# water-pump.net
KiCad netlist of a schematic drawn in EAGLE
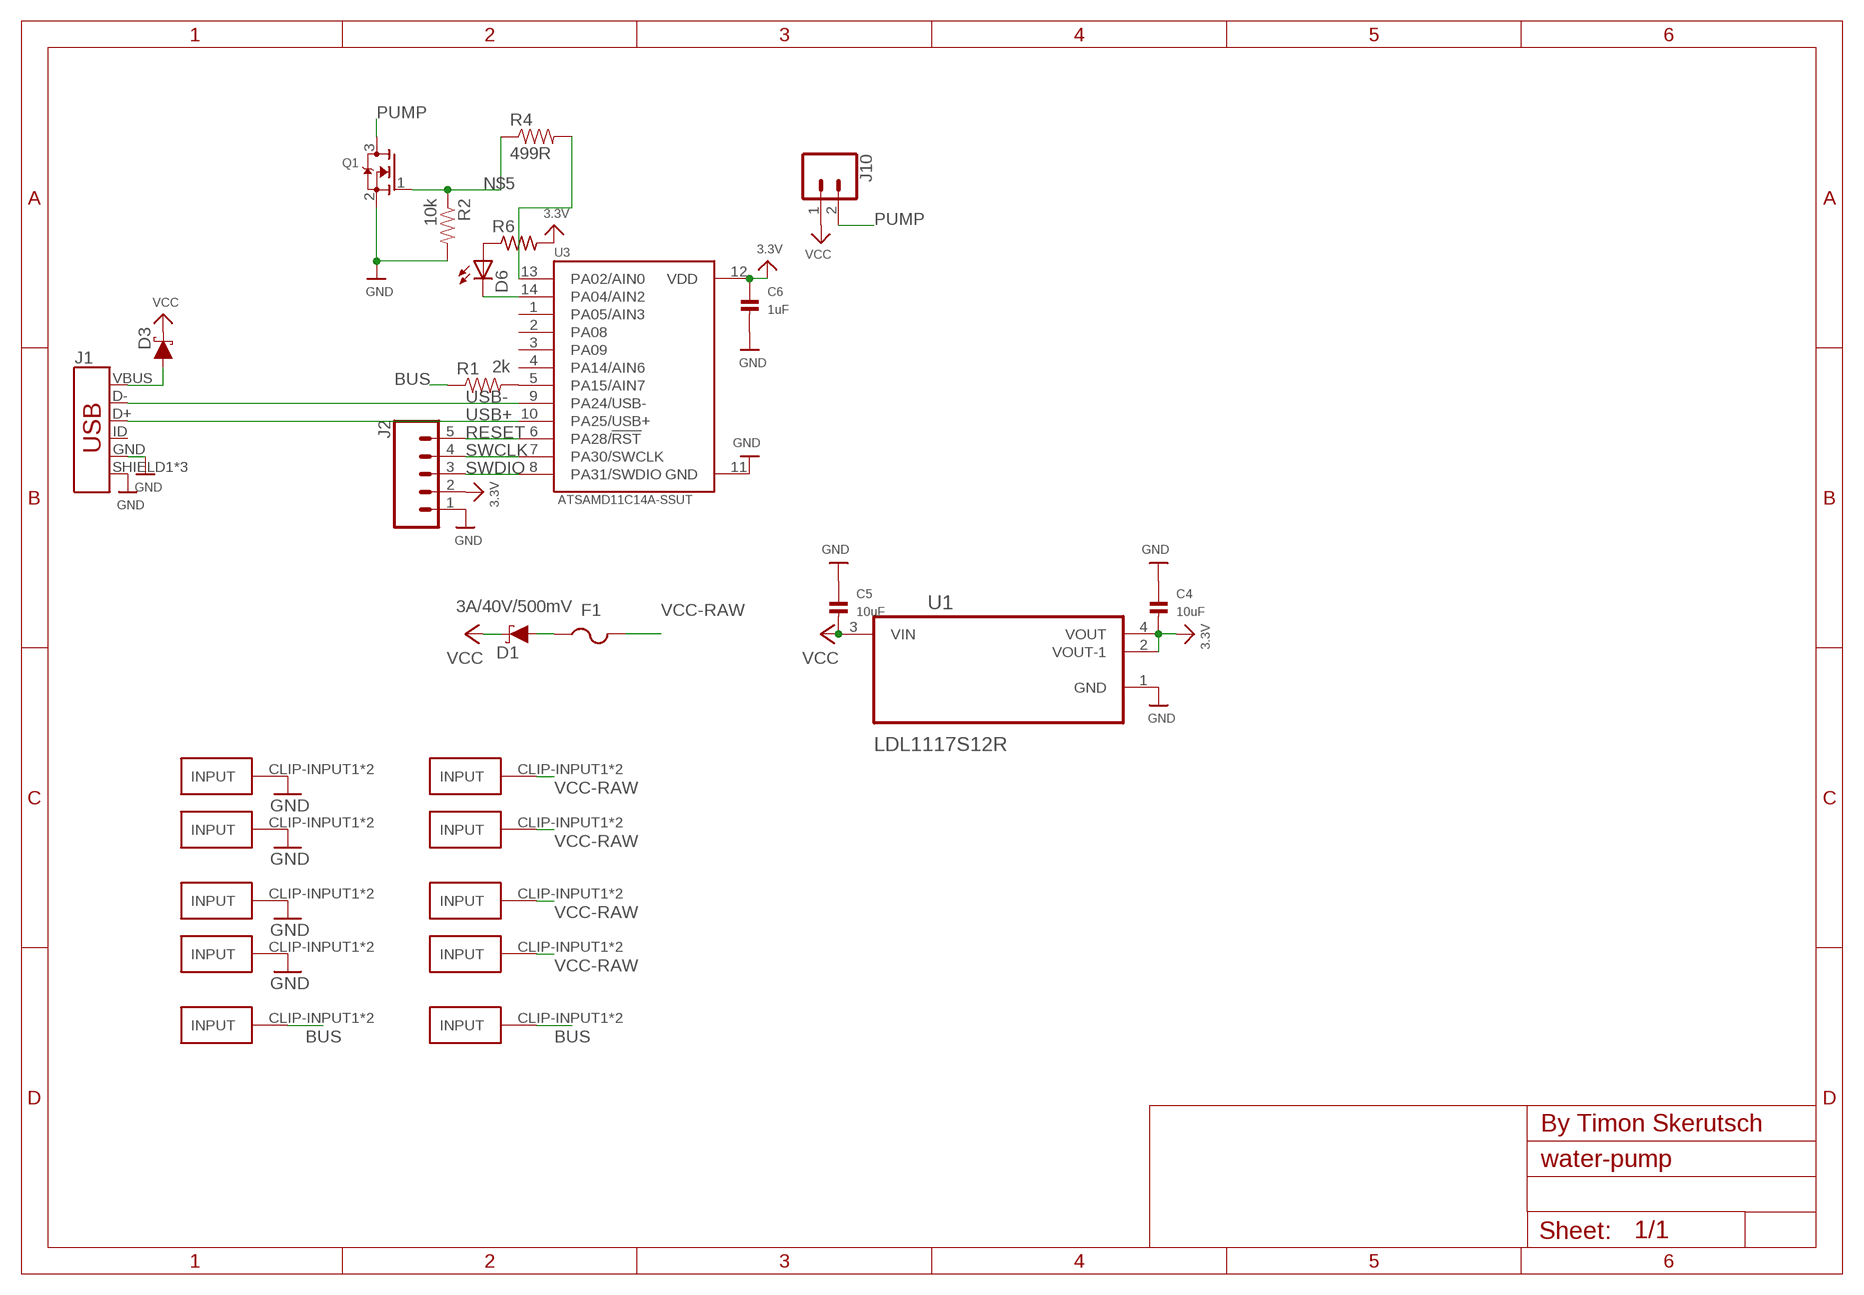
[diagram p0: schematic, sheet 1]

(export (version "E")
  (design (tool "Eeschema 10.0.6"))
  (components
    (comp (ref "C4")
      (value "10uF")
      (footprint "eagle-import:0805")
      (libsource (lib "eagle-import") (part "CAP_CERAMIC0805"))
    )
    (comp (ref "C5")
      (value "10uF")
      (footprint "eagle-import:0805")
      (libsource (lib "eagle-import") (part "CAP_CERAMIC0805"))
    )
    (comp (ref "C6")
      (value "1uF")
      (footprint "eagle-import:0603")
      (libsource (lib "eagle-import") (part "CAP_CERAMIC0603"))
    )
    (comp (ref "D1")
      (value "3A/40V/500mV")
      (footprint "eagle-import:SMA-DIODE")
      (libsource (lib "eagle-import") (part "DIODE-SCHOTTKY-B340A"))
    )
    (comp (ref "D3")
      (value "3A/40V/500mV")
      (footprint "eagle-import:SMA-DIODE")
      (libsource (lib "eagle-import") (part "DIODE-SCHOTTKY-B340A"))
    )
    (comp (ref "D6")
      (value "LEDCHIPLED_0805")
      (footprint "eagle-import:CHIPLED_0805")
      (libsource (lib "eagle-import") (part "LEDCHIPLED_0805"))
    )
    (comp (ref "F1")
      (value "PTCFUSE-1812")
      (footprint "eagle-import:1812")
      (libsource (lib "eagle-import") (part "PTCFUSE-1812"))
    )
    (comp (ref "GND-CLIP")
      (value "FUSE-HOLDER-5X20MM")
      (footprint "eagle-import:FUSE-HOLDER-5X20MM")
      (libsource (lib "eagle-import") (part "FUSE-HOLDER-5X20MM"))
    )
    (comp (ref "GND-CLIP1")
      (value "FUSE-HOLDER-5X20MM")
      (footprint "eagle-import:FUSE-HOLDER-5X20MM")
      (libsource (lib "eagle-import") (part "FUSE-HOLDER-5X20MM"))
    )
    (comp (ref "GND-CLIP2")
      (value "FUSE-HOLDER-5X20MM")
      (footprint "eagle-import:FUSE-HOLDER-5X20MM")
      (libsource (lib "eagle-import") (part "FUSE-HOLDER-5X20MM"))
    )
    (comp (ref "GND-CLIP3")
      (value "FUSE-HOLDER-5X20MM")
      (footprint "eagle-import:FUSE-HOLDER-5X20MM")
      (libsource (lib "eagle-import") (part "FUSE-HOLDER-5X20MM"))
    )
    (comp (ref "J1")
      (value "USB_MICRO-B_FEMALE-SMT")
      (footprint "eagle-import:USB-B-MICRO-SMD")
      (libsource (lib "eagle-import") (part "USB_MICRO-B_FEMALE-SMT"))
    )
    (comp (ref "J2")
      (value "CONN_05")
      (footprint "eagle-import:1X05")
      (libsource (lib "eagle-import") (part "CONN_05"))
    )
    (comp (ref "J10")
      (value "CONN_02PTH3")
      (footprint "eagle-import:1X02_LONGPADS")
      (libsource (lib "eagle-import") (part "CONN_02PTH3"))
    )
    (comp (ref "PWM-CLIP")
      (value "FUSE-HOLDER-5X20MM")
      (footprint "eagle-import:FUSE-HOLDER-5X20MM")
      (libsource (lib "eagle-import") (part "FUSE-HOLDER-5X20MM"))
    )
    (comp (ref "PWM-CLIP1")
      (value "FUSE-HOLDER-5X20MM")
      (footprint "eagle-import:FUSE-HOLDER-5X20MM")
      (libsource (lib "eagle-import") (part "FUSE-HOLDER-5X20MM"))
    )
    (comp (ref "Q1")
      (value "MOSFET-NWIDE")
      (footprint "eagle-import:SOT23-WIDE")
      (libsource (lib "eagle-import") (part "MOSFET-NWIDE"))
    )
    (comp (ref "R1")
      (value "2k")
      (footprint "eagle-import:1206")
      (libsource (lib "eagle-import") (part "RESISTOR1206"))
    )
    (comp (ref "R2")
      (value "10k")
      (footprint "eagle-import:1206")
      (libsource (lib "eagle-import") (part "RESISTOR1206"))
    )
    (comp (ref "R4")
      (value "499R")
      (footprint "eagle-import:1206")
      (libsource (lib "eagle-import") (part "RESISTOR1206"))
    )
    (comp (ref "R6")
      (value "R-US_R0805")
      (footprint "eagle-import:R0805")
      (libsource (lib "eagle-import") (part "R-US_R0805"))
    )
    (comp (ref "U1")
      (value "LDL1117S12R")
      (footprint "eagle-import:SOT230P700X180-4N")
      (fields (field (name "MF") "STMicroelectronics"))
      (libsource (lib "eagle-import") (part "LDL1117S12R"))
    )
    (comp (ref "U3")
      (value "ATSAMD11C14A-SSUT")
      (footprint "eagle-import:SOIC127P600X160-14N")
      (fields (field (name "MF") "Microchip"))
      (libsource (lib "eagle-import") (part "ATSAMD11C14A-SSUT"))
    )
    (comp (ref "VCC-CLIP")
      (value "FUSE-HOLDER-5X20MM")
      (footprint "eagle-import:FUSE-HOLDER-5X20MM")
      (libsource (lib "eagle-import") (part "FUSE-HOLDER-5X20MM"))
    )
    (comp (ref "VCC-CLIP1")
      (value "FUSE-HOLDER-5X20MM")
      (footprint "eagle-import:FUSE-HOLDER-5X20MM")
      (libsource (lib "eagle-import") (part "FUSE-HOLDER-5X20MM"))
    )
    (comp (ref "VCC-CLIP2")
      (value "FUSE-HOLDER-5X20MM")
      (footprint "eagle-import:FUSE-HOLDER-5X20MM")
      (libsource (lib "eagle-import") (part "FUSE-HOLDER-5X20MM"))
    )
    (comp (ref "VCC-CLIP3")
      (value "FUSE-HOLDER-5X20MM")
      (footprint "eagle-import:FUSE-HOLDER-5X20MM")
      (libsource (lib "eagle-import") (part "FUSE-HOLDER-5X20MM"))
    )
  )
  (nets
    (net (code "1") (name "/BUS") (class "Default")
      (node (ref "PWM-CLIP") (pin "CLIP-INPUT1") (pinfunction "INPUT_CLIP-INPUT1") (pintype "bidirectional"))
      (node (ref "PWM-CLIP") (pin "CLIP-INPUT2") (pinfunction "INPUT_CLIP-INPUT2") (pintype "bidirectional"))
      (node (ref "PWM-CLIP1") (pin "CLIP-INPUT1") (pinfunction "INPUT_CLIP-INPUT1") (pintype "bidirectional"))
      (node (ref "PWM-CLIP1") (pin "CLIP-INPUT2") (pinfunction "INPUT_CLIP-INPUT2") (pintype "bidirectional"))
      (node (ref "R1") (pin "1") (pinfunction "1_1") (pintype "passive"))
    )
    (net (code "2") (name "/N$5") (class "Default")
      (node (ref "Q1") (pin "1") (pinfunction "G_1") (pintype "bidirectional"))
      (node (ref "R2") (pin "1") (pinfunction "1_1") (pintype "passive"))
      (node (ref "R4") (pin "1") (pinfunction "1_1") (pintype "passive"))
    )
    (net (code "3") (name "/PUMP") (class "Default")
      (node (ref "J10") (pin "2") (pinfunction "2_2") (pintype "passive"))
      (node (ref "Q1") (pin "3") (pinfunction "D_3") (pintype "bidirectional"))
    )
    (net (code "4") (name "/RESET") (class "Default")
      (node (ref "J2") (pin "5") (pinfunction "5_5") (pintype "passive"))
      (node (ref "U3") (pin "6") (pinfunction "PA28/~{RST}_6") (pintype "bidirectional"))
    )
    (net (code "5") (name "/SWCLK") (class "Default")
      (node (ref "J2") (pin "4") (pinfunction "4_4") (pintype "passive"))
      (node (ref "U3") (pin "7") (pinfunction "PA30/SWCLK_7") (pintype "bidirectional"))
    )
    (net (code "6") (name "/SWDIO") (class "Default")
      (node (ref "J2") (pin "3") (pinfunction "3_3") (pintype "passive"))
      (node (ref "U3") (pin "8") (pinfunction "PA31/SWDIO_8") (pintype "bidirectional"))
    )
    (net (code "7") (name "/USB+") (class "Default")
      (node (ref "J1") (pin "D+") (pinfunction "D+_D+") (pintype "bidirectional"))
      (node (ref "U3") (pin "10") (pinfunction "PA25/USB+_10") (pintype "bidirectional"))
    )
    (net (code "8") (name "/USB-") (class "Default")
      (node (ref "J1") (pin "D-") (pinfunction "D-_D-") (pintype "bidirectional"))
      (node (ref "U3") (pin "9") (pinfunction "PA24/USB-_9") (pintype "bidirectional"))
    )
    (net (code "9") (name "/VCC-RAW") (class "Default")
      (node (ref "F1") (pin "2") (pinfunction "2_2") (pintype "passive"))
      (node (ref "VCC-CLIP") (pin "CLIP-INPUT1") (pinfunction "INPUT_CLIP-INPUT1") (pintype "bidirectional"))
      (node (ref "VCC-CLIP") (pin "CLIP-INPUT2") (pinfunction "INPUT_CLIP-INPUT2") (pintype "bidirectional"))
      (node (ref "VCC-CLIP1") (pin "CLIP-INPUT1") (pinfunction "INPUT_CLIP-INPUT1") (pintype "bidirectional"))
      (node (ref "VCC-CLIP1") (pin "CLIP-INPUT2") (pinfunction "INPUT_CLIP-INPUT2") (pintype "bidirectional"))
      (node (ref "VCC-CLIP2") (pin "CLIP-INPUT1") (pinfunction "INPUT_CLIP-INPUT1") (pintype "bidirectional"))
      (node (ref "VCC-CLIP2") (pin "CLIP-INPUT2") (pinfunction "INPUT_CLIP-INPUT2") (pintype "bidirectional"))
      (node (ref "VCC-CLIP3") (pin "CLIP-INPUT1") (pinfunction "INPUT_CLIP-INPUT1") (pintype "bidirectional"))
      (node (ref "VCC-CLIP3") (pin "CLIP-INPUT2") (pinfunction "INPUT_CLIP-INPUT2") (pintype "bidirectional"))
    )
    (net (code "10") (name "3.3V") (class "Default")
      (node (ref "C4") (pin "2") (pinfunction "P$2_2") (pintype "passive"))
      (node (ref "C6") (pin "1") (pinfunction "P$1_1") (pintype "passive"))
      (node (ref "J2") (pin "2") (pinfunction "2_2") (pintype "passive"))
      (node (ref "R6") (pin "2") (pinfunction "2_2") (pintype "passive"))
      (node (ref "U1") (pin "2") (pinfunction "VOUT-1_2") (pintype "output"))
      (node (ref "U1") (pin "4") (pinfunction "VOUT_4") (pintype "output"))
      (node (ref "U3") (pin "12") (pinfunction "VDD_12") (pintype "power_in"))
    )
    (net (code "11") (name "GND") (class "Default")
      (node (ref "C4") (pin "1") (pinfunction "P$1_1") (pintype "passive"))
      (node (ref "C5") (pin "1") (pinfunction "P$1_1") (pintype "passive"))
      (node (ref "C6") (pin "2") (pinfunction "P$2_2") (pintype "passive"))
      (node (ref "GND-CLIP") (pin "CLIP-INPUT1") (pinfunction "INPUT_CLIP-INPUT1") (pintype "bidirectional"))
      (node (ref "GND-CLIP") (pin "CLIP-INPUT2") (pinfunction "INPUT_CLIP-INPUT2") (pintype "bidirectional"))
      (node (ref "GND-CLIP1") (pin "CLIP-INPUT1") (pinfunction "INPUT_CLIP-INPUT1") (pintype "bidirectional"))
      (node (ref "GND-CLIP1") (pin "CLIP-INPUT2") (pinfunction "INPUT_CLIP-INPUT2") (pintype "bidirectional"))
      (node (ref "GND-CLIP2") (pin "CLIP-INPUT1") (pinfunction "INPUT_CLIP-INPUT1") (pintype "bidirectional"))
      (node (ref "GND-CLIP2") (pin "CLIP-INPUT2") (pinfunction "INPUT_CLIP-INPUT2") (pintype "bidirectional"))
      (node (ref "GND-CLIP3") (pin "CLIP-INPUT1") (pinfunction "INPUT_CLIP-INPUT1") (pintype "bidirectional"))
      (node (ref "GND-CLIP3") (pin "CLIP-INPUT2") (pinfunction "INPUT_CLIP-INPUT2") (pintype "bidirectional"))
      (node (ref "J1") (pin "GND") (pinfunction "GND_GND") (pintype "power_in"))
      (node (ref "J1") (pin "SHIELD1") (pinfunction "SHIELD_SHIELD1") (pintype "bidirectional"))
      (node (ref "J1") (pin "SHIELD2") (pinfunction "SHIELD_SHIELD2") (pintype "bidirectional"))
      (node (ref "J1") (pin "SHIELD3") (pinfunction "SHIELD_SHIELD3") (pintype "bidirectional"))
      (node (ref "J2") (pin "1") (pinfunction "1_1") (pintype "passive"))
      (node (ref "Q1") (pin "2") (pinfunction "S_2") (pintype "bidirectional"))
      (node (ref "R2") (pin "2") (pinfunction "2_2") (pintype "passive"))
      (node (ref "U1") (pin "1") (pinfunction "GND_1") (pintype "power_in"))
      (node (ref "U3") (pin "11") (pinfunction "GND_11") (pintype "power_in"))
    )
    (net (code "12") (name "Net-(D1-PadA)") (class "Default")
      (node (ref "D1") (pin "A") (pinfunction "A_A") (pintype "passive"))
      (node (ref "F1") (pin "1") (pinfunction "1_1") (pintype "passive"))
    )
    (net (code "13") (name "Net-(D3-PadA)") (class "Default")
      (node (ref "D3") (pin "A") (pinfunction "A_A") (pintype "passive"))
      (node (ref "J1") (pin "VBUS") (pinfunction "VBUS_VBUS") (pintype "power_in"))
    )
    (net (code "14") (name "Net-(D6-PadA)") (class "Default")
      (node (ref "D6") (pin "A") (pinfunction "A_A") (pintype "passive"))
      (node (ref "R6") (pin "1") (pinfunction "1_1") (pintype "passive"))
    )
    (net (code "15") (name "Net-(U3-PA02{slash}AIN0)") (class "Default")
      (node (ref "R4") (pin "2") (pinfunction "2_2") (pintype "passive"))
      (node (ref "U3") (pin "13") (pinfunction "PA02/AIN0_13") (pintype "bidirectional"))
    )
    (net (code "16") (name "Net-(U3-PA04{slash}AIN2)") (class "Default")
      (node (ref "D6") (pin "C") (pinfunction "C_C") (pintype "passive"))
      (node (ref "U3") (pin "14") (pinfunction "PA04/AIN2_14") (pintype "bidirectional"))
    )
    (net (code "17") (name "Net-(U3-PA15{slash}AIN7)") (class "Default")
      (node (ref "R1") (pin "2") (pinfunction "2_2") (pintype "passive"))
      (node (ref "U3") (pin "5") (pinfunction "PA15/AIN7_5") (pintype "bidirectional"))
    )
    (net (code "18") (name "VCC") (class "Default")
      (node (ref "C5") (pin "2") (pinfunction "P$2_2") (pintype "passive"))
      (node (ref "D1") (pin "C") (pinfunction "C_C") (pintype "passive"))
      (node (ref "D3") (pin "C") (pinfunction "C_C") (pintype "passive"))
      (node (ref "J10") (pin "1") (pinfunction "1_1") (pintype "passive"))
      (node (ref "U1") (pin "3") (pinfunction "VIN_3") (pintype "input"))
    )
    (net (code "19") (name "unconnected-(J1-PadID)") (class "Default")
      (node (ref "J1") (pin "ID") (pinfunction "ID_ID") (pintype "bidirectional"))
    )
    (net (code "20") (name "unconnected-(U3-PA05{slash}AIN3-Pad1)") (class "Default")
      (node (ref "U3") (pin "1") (pinfunction "PA05/AIN3_1") (pintype "bidirectional"))
    )
    (net (code "21") (name "unconnected-(U3-PA08-Pad2)") (class "Default")
      (node (ref "U3") (pin "2") (pinfunction "PA08_2") (pintype "bidirectional"))
    )
    (net (code "22") (name "unconnected-(U3-PA09-Pad3)") (class "Default")
      (node (ref "U3") (pin "3") (pinfunction "PA09_3") (pintype "bidirectional"))
    )
    (net (code "23") (name "unconnected-(U3-PA14{slash}AIN6-Pad4)") (class "Default")
      (node (ref "U3") (pin "4") (pinfunction "PA14/AIN6_4") (pintype "bidirectional"))
    )
  )
)
